# PCM5102a_FG_Small.net
KiCad netlist of a schematic drawn in EAGLE
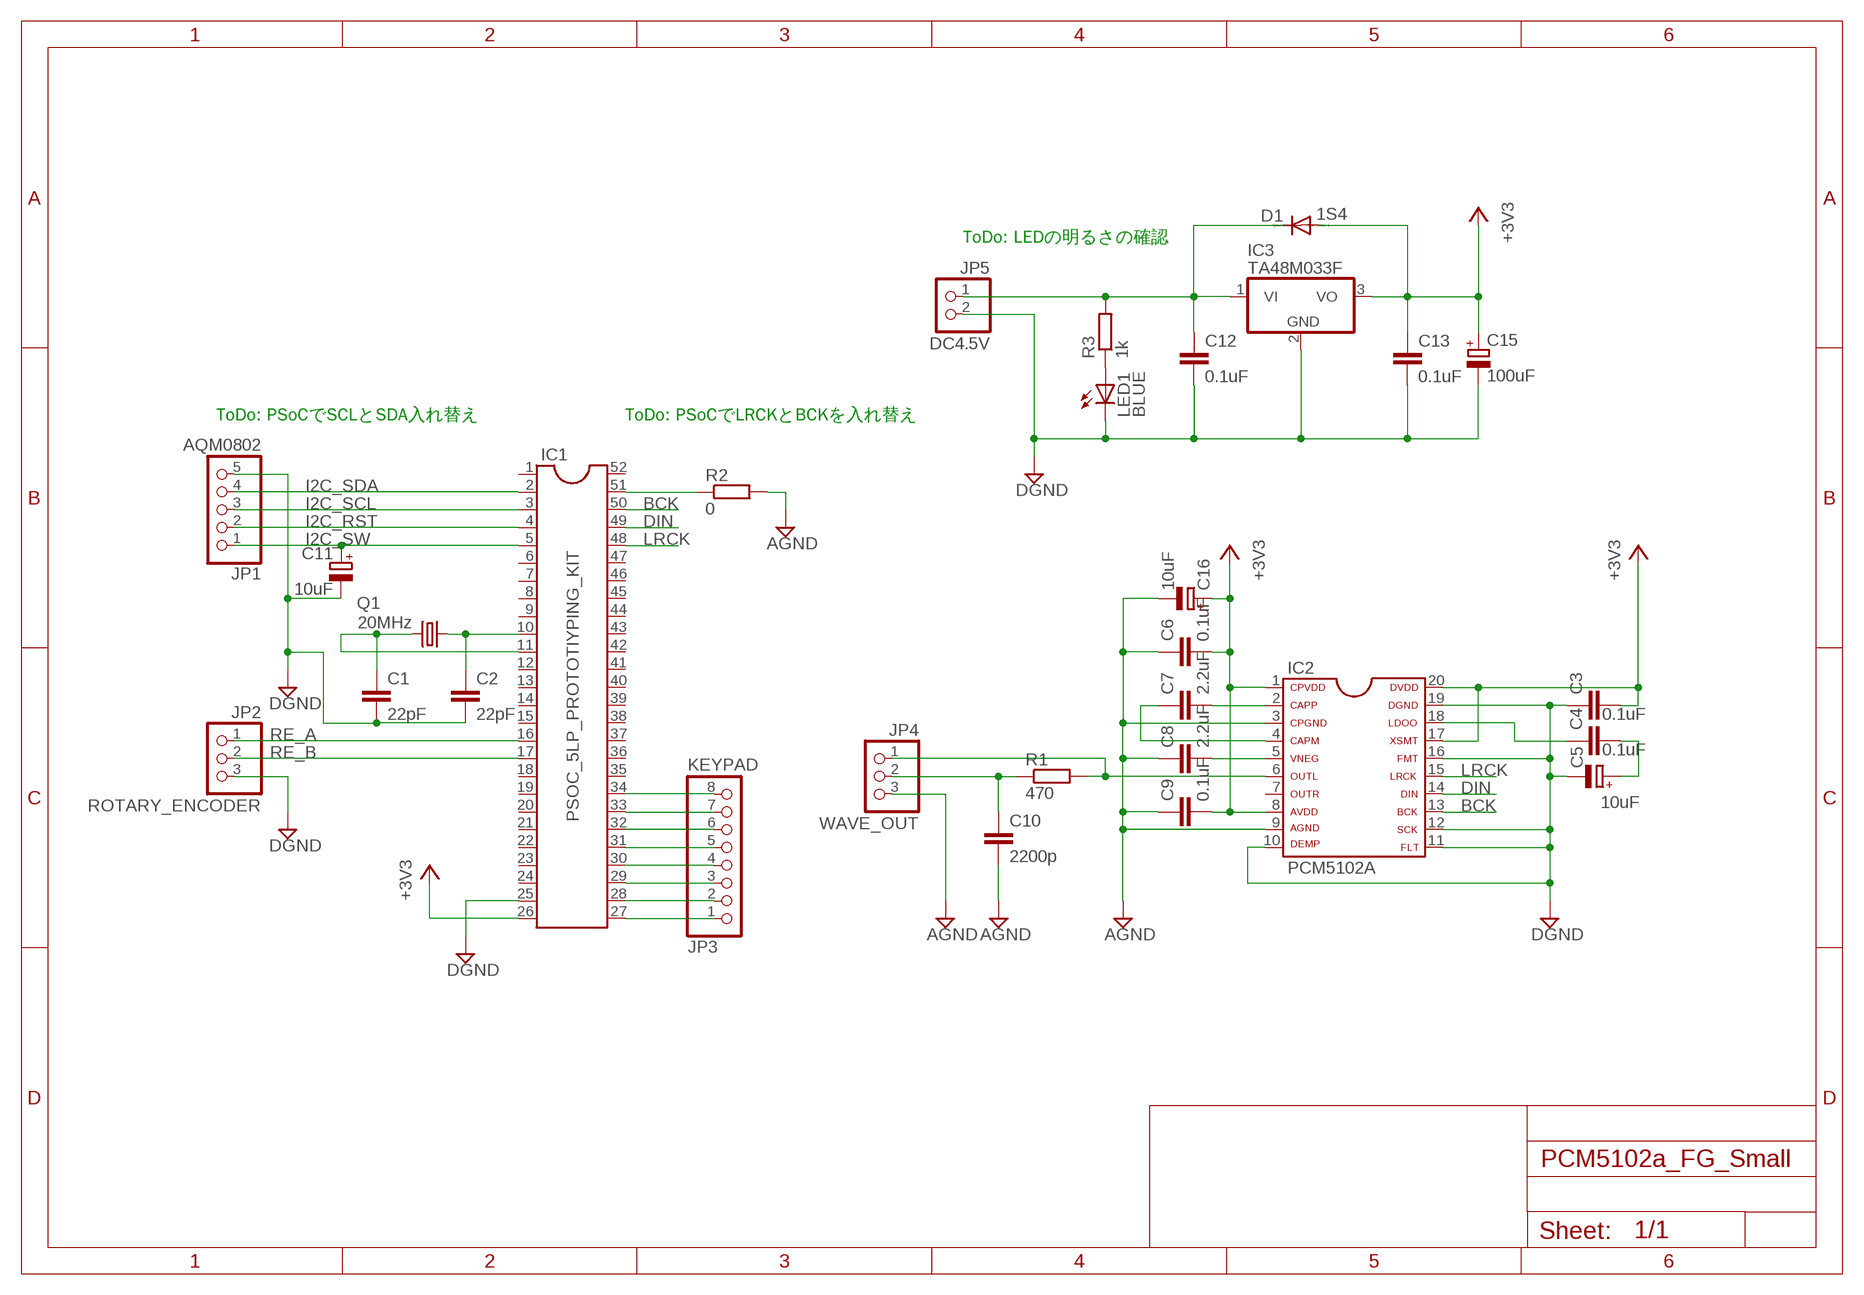
[diagram p0: schematic, sheet 1]

(export (version "E")
  (design (tool "Eeschema 10.0.6"))
  (components
    (comp (ref "C1")
      (value "22pF")
      (footprint "eagle-import:C025-024X044")
      (libsource (lib "eagle-import") (part "C-EU025-024X044"))
    )
    (comp (ref "C2")
      (value "22pF")
      (footprint "eagle-import:C025-024X044")
      (libsource (lib "eagle-import") (part "C-EU025-024X044"))
    )
    (comp (ref "C3")
      (value "0.1uF")
      (footprint "eagle-import:C025-024X044")
      (libsource (lib "eagle-import") (part "C-EU025-024X044"))
    )
    (comp (ref "C4")
      (value "0.1uF")
      (footprint "eagle-import:C025-024X044")
      (libsource (lib "eagle-import") (part "C-EU025-024X044"))
    )
    (comp (ref "C5")
      (value "10uF")
      (footprint "eagle-import:E2,5-5")
      (libsource (lib "eagle-import") (part "CPOL-EUE2.5-5"))
    )
    (comp (ref "C6")
      (value "0.1uF")
      (footprint "eagle-import:C025-024X044")
      (libsource (lib "eagle-import") (part "C-EU025-024X044"))
    )
    (comp (ref "C7")
      (value "2.2uF")
      (footprint "eagle-import:C075-063X106")
      (libsource (lib "eagle-import") (part "C-EU075-063X106"))
    )
    (comp (ref "C8")
      (value "2.2uF")
      (footprint "eagle-import:C075-063X106")
      (libsource (lib "eagle-import") (part "C-EU075-063X106"))
    )
    (comp (ref "C9")
      (value "0.1uF")
      (footprint "eagle-import:C025-024X044")
      (libsource (lib "eagle-import") (part "C-EU025-024X044"))
    )
    (comp (ref "C10")
      (value "2200p")
      (footprint "eagle-import:C050-035X075")
      (libsource (lib "eagle-import") (part "C-EU050-035X075"))
    )
    (comp (ref "C11")
      (value "10uF")
      (footprint "eagle-import:E2,5-5")
      (libsource (lib "eagle-import") (part "CPOL-EUE2.5-5"))
    )
    (comp (ref "C12")
      (value "0.1uF")
      (footprint "eagle-import:C025-024X044")
      (libsource (lib "eagle-import") (part "C-EU025-024X044"))
    )
    (comp (ref "C13")
      (value "0.1uF")
      (footprint "eagle-import:C025-024X044")
      (libsource (lib "eagle-import") (part "C-EU025-024X044"))
    )
    (comp (ref "C15")
      (value "100uF")
      (footprint "eagle-import:E2,5-7")
      (libsource (lib "eagle-import") (part "CPOL-EUE2.5-7"))
    )
    (comp (ref "C16")
      (value "10uF")
      (footprint "eagle-import:E2,5-5")
      (libsource (lib "eagle-import") (part "CPOL-EUE2.5-5"))
    )
    (comp (ref "D1")
      (value "1S4")
      (footprint "eagle-import:DO41-10")
      (libsource (lib "eagle-import") (part "1N4004"))
    )
    (comp (ref "IC1")
      (value "PSOC_5LP_PROTOTIYPING_KIT")
      (footprint "eagle-import:DIL52-8")
      (libsource (lib "eagle-import") (part "PSOC_5LP_PROTOTIYPING_KIT"))
    )
    (comp (ref "IC2")
      (value "PCM5102A")
      (footprint "eagle-import:DIL20-6")
      (libsource (lib "eagle-import") (part "PCM5102A"))
    )
    (comp (ref "IC3")
      (value "TA48M033F")
      (footprint "eagle-import:TO220V")
      (libsource (lib "eagle-import") (part "78TV05"))
    )
    (comp (ref "JP1")
      (value "AQM0802")
      (footprint "eagle-import:1X05")
      (libsource (lib "eagle-import") (part "PINHD-1X5"))
    )
    (comp (ref "JP2")
      (value "ROTARY_ENCODER")
      (footprint "eagle-import:1X03")
      (libsource (lib "eagle-import") (part "PINHD-1X3"))
    )
    (comp (ref "JP3")
      (value "KEYPAD")
      (footprint "eagle-import:1X08")
      (libsource (lib "eagle-import") (part "PINHD-1X8"))
    )
    (comp (ref "JP4")
      (value "WAVE_OUT")
      (footprint "eagle-import:1X03")
      (libsource (lib "eagle-import") (part "PINHD-1X3"))
    )
    (comp (ref "JP5")
      (value "DC4.5V")
      (footprint "eagle-import:1X02")
      (libsource (lib "eagle-import") (part "PINHD-1X2"))
    )
    (comp (ref "LED1")
      (value "BLUE")
      (footprint "eagle-import:LED3MM")
      (libsource (lib "eagle-import") (part "LED3MM"))
    )
    (comp (ref "Q1")
      (value "20MHz")
      (footprint "eagle-import:HC49_S")
      (libsource (lib "eagle-import") (part "CRYSTALHC49S"))
    )
    (comp (ref "R1")
      (value "470")
      (footprint "eagle-import:0207_7")
      (libsource (lib "eagle-import") (part "R-EU_0207/7"))
    )
    (comp (ref "R2")
      (value "0")
      (footprint "eagle-import:0207_7")
      (libsource (lib "eagle-import") (part "resistor_R-EU_0207/7"))
    )
    (comp (ref "R3")
      (value "1k")
      (footprint "eagle-import:0207_7")
      (libsource (lib "eagle-import") (part "resistor_R-EU_0207/7"))
    )
  )
  (nets
    (net (code "1") (name "+3V3") (class "Default")
      (node (ref "C13") (pin "1") (pinfunction "1_1") (pintype "passive"))
      (node (ref "C15") (pin "+") (pinfunction "+_+") (pintype "passive"))
      (node (ref "C16") (pin "+") (pinfunction "+_+") (pintype "passive"))
      (node (ref "C3") (pin "2") (pinfunction "2_2") (pintype "passive"))
      (node (ref "C6") (pin "2") (pinfunction "2_2") (pintype "passive"))
      (node (ref "C9") (pin "2") (pinfunction "2_2") (pintype "passive"))
      (node (ref "D1") (pin "A") (pinfunction "A_A") (pintype "passive"))
      (node (ref "IC1") (pin "26") (pinfunction "26_26") (pintype "passive"))
      (node (ref "IC2") (pin "1") (pinfunction "1_1") (pintype "passive"))
      (node (ref "IC2") (pin "17") (pinfunction "17_17") (pintype "passive"))
      (node (ref "IC2") (pin "20") (pinfunction "20_20") (pintype "passive"))
      (node (ref "IC2") (pin "8") (pinfunction "8_8") (pintype "passive"))
      (node (ref "IC3") (pin "3") (pinfunction "VO_3") (pintype "passive"))
    )
    (net (code "2") (name "/BCK") (class "Default")
      (node (ref "IC1") (pin "50") (pinfunction "50_50") (pintype "passive"))
      (node (ref "IC2") (pin "13") (pinfunction "13_13") (pintype "passive"))
    )
    (net (code "3") (name "/DIN") (class "Default")
      (node (ref "IC1") (pin "49") (pinfunction "49_49") (pintype "passive"))
      (node (ref "IC2") (pin "14") (pinfunction "14_14") (pintype "passive"))
    )
    (net (code "4") (name "/I2C_RST") (class "Default")
      (node (ref "IC1") (pin "4") (pinfunction "4_4") (pintype "passive"))
      (node (ref "JP1") (pin "2") (pinfunction "2_2") (pintype "passive"))
    )
    (net (code "5") (name "/I2C_SCL") (class "Default")
      (node (ref "IC1") (pin "3") (pinfunction "3_3") (pintype "passive"))
      (node (ref "JP1") (pin "3") (pinfunction "3_3") (pintype "passive"))
    )
    (net (code "6") (name "/I2C_SDA") (class "Default")
      (node (ref "IC1") (pin "2") (pinfunction "2_2") (pintype "passive"))
      (node (ref "JP1") (pin "4") (pinfunction "4_4") (pintype "passive"))
    )
    (net (code "7") (name "/I2C_SW") (class "Default")
      (node (ref "C11") (pin "+") (pinfunction "+_+") (pintype "passive"))
      (node (ref "IC1") (pin "5") (pinfunction "5_5") (pintype "passive"))
      (node (ref "JP1") (pin "1") (pinfunction "1_1") (pintype "passive"))
    )
    (net (code "8") (name "/LRCK") (class "Default")
      (node (ref "IC1") (pin "48") (pinfunction "48_48") (pintype "passive"))
      (node (ref "IC2") (pin "15") (pinfunction "15_15") (pintype "passive"))
    )
    (net (code "9") (name "/RE_A") (class "Default")
      (node (ref "IC1") (pin "16") (pinfunction "16_16") (pintype "passive"))
      (node (ref "JP2") (pin "1") (pinfunction "1_1") (pintype "passive"))
    )
    (net (code "10") (name "/RE_B") (class "Default")
      (node (ref "IC1") (pin "17") (pinfunction "17_17") (pintype "passive"))
      (node (ref "JP2") (pin "2") (pinfunction "2_2") (pintype "passive"))
    )
    (net (code "11") (name "AGND") (class "Default")
      (node (ref "C10") (pin "2") (pinfunction "2_2") (pintype "passive"))
      (node (ref "C16") (pin "-") (pinfunction "-_-") (pintype "passive"))
      (node (ref "C6") (pin "1") (pinfunction "1_1") (pintype "passive"))
      (node (ref "C8") (pin "1") (pinfunction "1_1") (pintype "passive"))
      (node (ref "C9") (pin "1") (pinfunction "1_1") (pintype "passive"))
      (node (ref "IC2") (pin "3") (pinfunction "3_3") (pintype "passive"))
      (node (ref "IC2") (pin "9") (pinfunction "9_9") (pintype "passive"))
      (node (ref "JP4") (pin "3") (pinfunction "3_3") (pintype "passive"))
      (node (ref "R2") (pin "2") (pinfunction "2_2") (pintype "passive"))
    )
    (net (code "12") (name "DGND") (class "Default")
      (node (ref "C1") (pin "2") (pinfunction "2_2") (pintype "passive"))
      (node (ref "C11") (pin "-") (pinfunction "-_-") (pintype "passive"))
      (node (ref "C12") (pin "2") (pinfunction "2_2") (pintype "passive"))
      (node (ref "C13") (pin "2") (pinfunction "2_2") (pintype "passive"))
      (node (ref "C15") (pin "-") (pinfunction "-_-") (pintype "passive"))
      (node (ref "C2") (pin "2") (pinfunction "2_2") (pintype "passive"))
      (node (ref "C3") (pin "1") (pinfunction "1_1") (pintype "passive"))
      (node (ref "C5") (pin "-") (pinfunction "-_-") (pintype "passive"))
      (node (ref "IC1") (pin "25") (pinfunction "25_25") (pintype "passive"))
      (node (ref "IC2") (pin "10") (pinfunction "10_10") (pintype "passive"))
      (node (ref "IC2") (pin "11") (pinfunction "11_11") (pintype "passive"))
      (node (ref "IC2") (pin "12") (pinfunction "12_12") (pintype "passive"))
      (node (ref "IC2") (pin "16") (pinfunction "16_16") (pintype "passive"))
      (node (ref "IC2") (pin "19") (pinfunction "19_19") (pintype "passive"))
      (node (ref "IC3") (pin "2") (pinfunction "GND_2") (pintype "passive"))
      (node (ref "JP1") (pin "5") (pinfunction "5_5") (pintype "passive"))
      (node (ref "JP2") (pin "3") (pinfunction "3_3") (pintype "passive"))
      (node (ref "JP5") (pin "2") (pinfunction "2_2") (pintype "passive"))
      (node (ref "LED1") (pin "K") (pinfunction "C_K") (pintype "passive"))
    )
    (net (code "13") (name "Net-(C1-Pad1)") (class "Default")
      (node (ref "C1") (pin "1") (pinfunction "1_1") (pintype "passive"))
      (node (ref "IC1") (pin "11") (pinfunction "11_11") (pintype "passive"))
      (node (ref "Q1") (pin "2") (pinfunction "2_2") (pintype "passive"))
    )
    (net (code "14") (name "Net-(C2-Pad1)") (class "Default")
      (node (ref "C2") (pin "1") (pinfunction "1_1") (pintype "passive"))
      (node (ref "IC1") (pin "10") (pinfunction "10_10") (pintype "passive"))
      (node (ref "Q1") (pin "1") (pinfunction "1_1") (pintype "passive"))
    )
    (net (code "15") (name "Net-(C4-Pad1)") (class "Default")
      (node (ref "C4") (pin "1") (pinfunction "1_1") (pintype "passive"))
      (node (ref "IC2") (pin "18") (pinfunction "18_18") (pintype "passive"))
    )
    (net (code "16") (name "Net-(C4-Pad2)") (class "Default")
      (node (ref "C4") (pin "2") (pinfunction "2_2") (pintype "passive"))
      (node (ref "C5") (pin "+") (pinfunction "+_+") (pintype "passive"))
    )
    (net (code "17") (name "Net-(C7-Pad1)") (class "Default")
      (node (ref "C7") (pin "1") (pinfunction "1_1") (pintype "passive"))
      (node (ref "IC2") (pin "4") (pinfunction "4_4") (pintype "passive"))
    )
    (net (code "18") (name "Net-(C7-Pad2)") (class "Default")
      (node (ref "C7") (pin "2") (pinfunction "2_2") (pintype "passive"))
      (node (ref "IC2") (pin "2") (pinfunction "2_2") (pintype "passive"))
    )
    (net (code "19") (name "Net-(C8-Pad2)") (class "Default")
      (node (ref "C8") (pin "2") (pinfunction "2_2") (pintype "passive"))
      (node (ref "IC2") (pin "5") (pinfunction "5_5") (pintype "passive"))
    )
    (net (code "20") (name "Net-(C10-Pad1)") (class "Default")
      (node (ref "C10") (pin "1") (pinfunction "1_1") (pintype "passive"))
      (node (ref "JP4") (pin "2") (pinfunction "2_2") (pintype "passive"))
      (node (ref "R1") (pin "1") (pinfunction "1_1") (pintype "passive"))
    )
    (net (code "21") (name "Net-(IC1-Pad27)") (class "Default")
      (node (ref "IC1") (pin "27") (pinfunction "27_27") (pintype "passive"))
      (node (ref "JP3") (pin "1") (pinfunction "1_1") (pintype "passive"))
    )
    (net (code "22") (name "Net-(IC1-Pad28)") (class "Default")
      (node (ref "IC1") (pin "28") (pinfunction "28_28") (pintype "passive"))
      (node (ref "JP3") (pin "2") (pinfunction "2_2") (pintype "passive"))
    )
    (net (code "23") (name "Net-(IC1-Pad29)") (class "Default")
      (node (ref "IC1") (pin "29") (pinfunction "29_29") (pintype "passive"))
      (node (ref "JP3") (pin "3") (pinfunction "3_3") (pintype "passive"))
    )
    (net (code "24") (name "Net-(IC1-Pad30)") (class "Default")
      (node (ref "IC1") (pin "30") (pinfunction "30_30") (pintype "passive"))
      (node (ref "JP3") (pin "4") (pinfunction "4_4") (pintype "passive"))
    )
    (net (code "25") (name "Net-(IC1-Pad31)") (class "Default")
      (node (ref "IC1") (pin "31") (pinfunction "31_31") (pintype "passive"))
      (node (ref "JP3") (pin "5") (pinfunction "5_5") (pintype "passive"))
    )
    (net (code "26") (name "Net-(IC1-Pad32)") (class "Default")
      (node (ref "IC1") (pin "32") (pinfunction "32_32") (pintype "passive"))
      (node (ref "JP3") (pin "6") (pinfunction "6_6") (pintype "passive"))
    )
    (net (code "27") (name "Net-(IC1-Pad33)") (class "Default")
      (node (ref "IC1") (pin "33") (pinfunction "33_33") (pintype "passive"))
      (node (ref "JP3") (pin "7") (pinfunction "7_7") (pintype "passive"))
    )
    (net (code "28") (name "Net-(IC1-Pad34)") (class "Default")
      (node (ref "IC1") (pin "34") (pinfunction "34_34") (pintype "passive"))
      (node (ref "JP3") (pin "8") (pinfunction "8_8") (pintype "passive"))
    )
    (net (code "29") (name "Net-(IC1-Pad51)") (class "Default")
      (node (ref "IC1") (pin "51") (pinfunction "51_51") (pintype "passive"))
      (node (ref "R2") (pin "1") (pinfunction "1_1") (pintype "passive"))
    )
    (net (code "30") (name "Net-(IC2-Pad6)") (class "Default")
      (node (ref "IC2") (pin "6") (pinfunction "6_6") (pintype "passive"))
      (node (ref "JP4") (pin "1") (pinfunction "1_1") (pintype "passive"))
      (node (ref "R1") (pin "2") (pinfunction "2_2") (pintype "passive"))
    )
    (net (code "31") (name "Net-(IC3-VI)") (class "Default")
      (node (ref "C12") (pin "1") (pinfunction "1_1") (pintype "passive"))
      (node (ref "D1") (pin "C") (pinfunction "C_C") (pintype "passive"))
      (node (ref "IC3") (pin "1") (pinfunction "VI_1") (pintype "input"))
      (node (ref "JP5") (pin "1") (pinfunction "1_1") (pintype "passive"))
      (node (ref "R3") (pin "2") (pinfunction "2_2") (pintype "passive"))
    )
    (net (code "32") (name "Net-(LED1-PadA)") (class "Default")
      (node (ref "LED1") (pin "A") (pinfunction "A_A") (pintype "passive"))
      (node (ref "R3") (pin "1") (pinfunction "1_1") (pintype "passive"))
    )
    (net (code "33") (name "unconnected-(IC1-Pad1)") (class "Default")
      (node (ref "IC1") (pin "1") (pinfunction "1_1") (pintype "passive"))
    )
    (net (code "34") (name "unconnected-(IC1-Pad6)") (class "Default")
      (node (ref "IC1") (pin "6") (pinfunction "6_6") (pintype "passive"))
    )
    (net (code "35") (name "unconnected-(IC1-Pad7)") (class "Default")
      (node (ref "IC1") (pin "7") (pinfunction "7_7") (pintype "passive"))
    )
    (net (code "36") (name "unconnected-(IC1-Pad8)") (class "Default")
      (node (ref "IC1") (pin "8") (pinfunction "8_8") (pintype "passive"))
    )
    (net (code "37") (name "unconnected-(IC1-Pad9)") (class "Default")
      (node (ref "IC1") (pin "9") (pinfunction "9_9") (pintype "passive"))
    )
    (net (code "38") (name "unconnected-(IC1-Pad12)") (class "Default")
      (node (ref "IC1") (pin "12") (pinfunction "12_12") (pintype "passive"))
    )
    (net (code "39") (name "unconnected-(IC1-Pad13)") (class "Default")
      (node (ref "IC1") (pin "13") (pinfunction "13_13") (pintype "passive"))
    )
    (net (code "40") (name "unconnected-(IC1-Pad14)") (class "Default")
      (node (ref "IC1") (pin "14") (pinfunction "14_14") (pintype "passive"))
    )
    (net (code "41") (name "unconnected-(IC1-Pad15)") (class "Default")
      (node (ref "IC1") (pin "15") (pinfunction "15_15") (pintype "passive"))
    )
    (net (code "42") (name "unconnected-(IC1-Pad18)") (class "Default")
      (node (ref "IC1") (pin "18") (pinfunction "18_18") (pintype "passive"))
    )
    (net (code "43") (name "unconnected-(IC1-Pad19)") (class "Default")
      (node (ref "IC1") (pin "19") (pinfunction "19_19") (pintype "passive"))
    )
    (net (code "44") (name "unconnected-(IC1-Pad20)") (class "Default")
      (node (ref "IC1") (pin "20") (pinfunction "20_20") (pintype "passive"))
    )
    (net (code "45") (name "unconnected-(IC1-Pad21)") (class "Default")
      (node (ref "IC1") (pin "21") (pinfunction "21_21") (pintype "passive"))
    )
    (net (code "46") (name "unconnected-(IC1-Pad22)") (class "Default")
      (node (ref "IC1") (pin "22") (pinfunction "22_22") (pintype "passive"))
    )
    (net (code "47") (name "unconnected-(IC1-Pad23)") (class "Default")
      (node (ref "IC1") (pin "23") (pinfunction "23_23") (pintype "passive"))
    )
    (net (code "48") (name "unconnected-(IC1-Pad24)") (class "Default")
      (node (ref "IC1") (pin "24") (pinfunction "24_24") (pintype "passive"))
    )
    (net (code "49") (name "unconnected-(IC1-Pad35)") (class "Default")
      (node (ref "IC1") (pin "35") (pinfunction "35_35") (pintype "passive"))
    )
    (net (code "50") (name "unconnected-(IC1-Pad36)") (class "Default")
      (node (ref "IC1") (pin "36") (pinfunction "36_36") (pintype "passive"))
    )
    (net (code "51") (name "unconnected-(IC1-Pad37)") (class "Default")
      (node (ref "IC1") (pin "37") (pinfunction "37_37") (pintype "passive"))
    )
    (net (code "52") (name "unconnected-(IC1-Pad38)") (class "Default")
      (node (ref "IC1") (pin "38") (pinfunction "38_38") (pintype "passive"))
    )
    (net (code "53") (name "unconnected-(IC1-Pad39)") (class "Default")
      (node (ref "IC1") (pin "39") (pinfunction "39_39") (pintype "passive"))
    )
    (net (code "54") (name "unconnected-(IC1-Pad40)") (class "Default")
      (node (ref "IC1") (pin "40") (pinfunction "40_40") (pintype "passive"))
    )
    (net (code "55") (name "unconnected-(IC1-Pad41)") (class "Default")
      (node (ref "IC1") (pin "41") (pinfunction "41_41") (pintype "passive"))
    )
    (net (code "56") (name "unconnected-(IC1-Pad42)") (class "Default")
      (node (ref "IC1") (pin "42") (pinfunction "42_42") (pintype "passive"))
    )
    (net (code "57") (name "unconnected-(IC1-Pad43)") (class "Default")
      (node (ref "IC1") (pin "43") (pinfunction "43_43") (pintype "passive"))
    )
    (net (code "58") (name "unconnected-(IC1-Pad44)") (class "Default")
      (node (ref "IC1") (pin "44") (pinfunction "44_44") (pintype "passive"))
    )
    (net (code "59") (name "unconnected-(IC1-Pad45)") (class "Default")
      (node (ref "IC1") (pin "45") (pinfunction "45_45") (pintype "passive"))
    )
    (net (code "60") (name "unconnected-(IC1-Pad46)") (class "Default")
      (node (ref "IC1") (pin "46") (pinfunction "46_46") (pintype "passive"))
    )
    (net (code "61") (name "unconnected-(IC1-Pad47)") (class "Default")
      (node (ref "IC1") (pin "47") (pinfunction "47_47") (pintype "passive"))
    )
    (net (code "62") (name "unconnected-(IC1-Pad52)") (class "Default")
      (node (ref "IC1") (pin "52") (pinfunction "52_52") (pintype "passive"))
    )
    (net (code "63") (name "unconnected-(IC2-Pad7)") (class "Default")
      (node (ref "IC2") (pin "7") (pinfunction "7_7") (pintype "passive"))
    )
  )
)
